# PLL2.net
KiCad netlist of a schematic drawn in Altium Designer
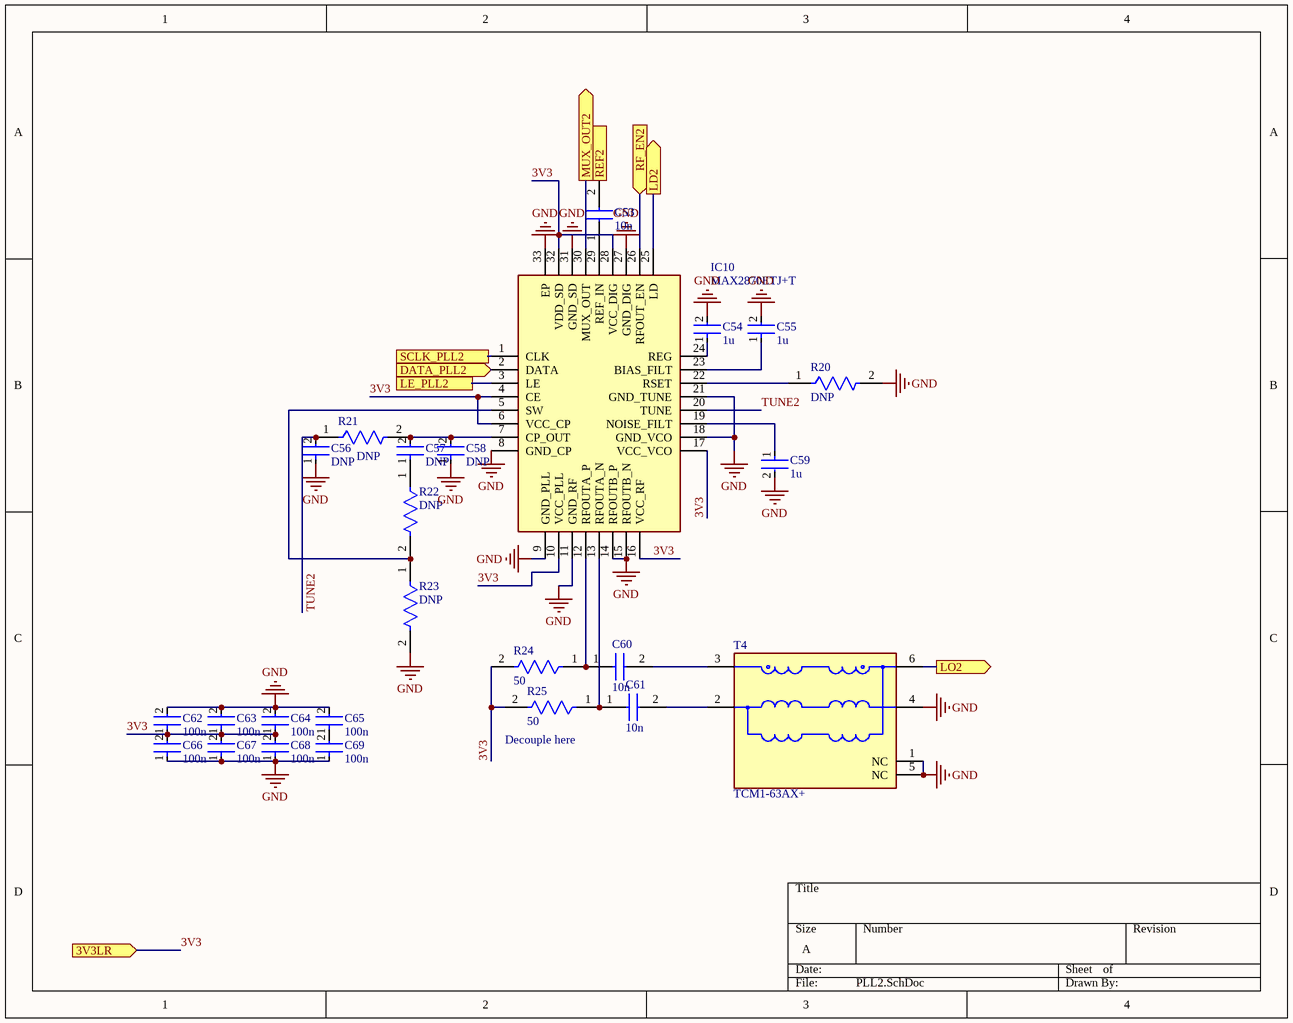
[diagram p0: PLL2.SchDoc]

(export (version "E")
  (design (tool "Eeschema 10.0.6"))
  (components
    (comp (ref "C53")
      (value "10n")
      (footprint "SamacSys:CAPC1005X61N")
      (description "Capacitor")
      (fields
        (field (name "MANUFACTURER_PART_NUMBER") "520L103KT16T")
        (field (name "MOUSER PART NUMBER") "581-520L103KT16T")
      )
      (libsource (lib "*") (part "520L103KT16T"))
    )
    (comp (ref "C54")
      (value "1u")
      (footprint "FP-GRM155-0_1-MFG")
      (description "Chip Multilayer Ceramic Capacitors for General Purpose, 0402, 1.0uF, X5R, 15%, 10%, 50V")
      (libsource (lib "Altium Content Vault") (part "11868f565c42a9108669ba33697ecf6"))
    )
    (comp (ref "C55")
      (value "1u")
      (footprint "FP-GRM155-0_1-MFG")
      (description "Chip Multilayer Ceramic Capacitors for General Purpose, 0402, 1.0uF, X5R, 15%, 10%, 50V")
      (libsource (lib "Altium Content Vault") (part "11868f565c42a9108669ba33697ecf6"))
    )
    (comp (ref "C56")
      (value "DNP")
      (footprint "FP-GRM155-0_05-IPC_C")
      (description "Chip Multilayer Ceramic Capacitors for General Purpose, 0402, 0.10uF, X5R, 15%, 10%, 100V")
      (fields (field (name "TOLERANCE") "10%"))
      (libsource (lib "Altium Content Vault") (part "02cd4be3c70576c341d710602a673aa"))
    )
    (comp (ref "C57")
      (value "DNP")
      (footprint "FP-GRM155-0_05-IPC_C")
      (description "Chip Multilayer Ceramic Capacitors for General Purpose, 0402, 0.10uF, X5R, 15%, 10%, 100V")
      (fields (field (name "TOLERANCE") "10%"))
      (libsource (lib "Altium Content Vault") (part "02cd4be3c70576c341d710602a673aa"))
    )
    (comp (ref "C58")
      (value "DNP")
      (footprint "FP-GRM155-0_05-IPC_C")
      (description "Chip Multilayer Ceramic Capacitors for General Purpose, 0402, 0.10uF, X5R, 15%, 10%, 100V")
      (fields (field (name "TOLERANCE") "10%"))
      (libsource (lib "Altium Content Vault") (part "02cd4be3c70576c341d710602a673aa"))
    )
    (comp (ref "C59")
      (value "1u")
      (footprint "FP-GRM155-0_1-MFG")
      (description "Chip Multilayer Ceramic Capacitors for General Purpose, 0402, 1.0uF, X5R, 15%, 10%, 50V")
      (libsource (lib "Altium Content Vault") (part "11868f565c42a9108669ba33697ecf6"))
    )
    (comp (ref "C60")
      (value "10n")
      (footprint "SamacSys:CAPC1005X61N")
      (description "Capacitor")
      (fields
        (field (name "MANUFACTURER_PART_NUMBER") "520L103KT16T")
        (field (name "MOUSER PART NUMBER") "581-520L103KT16T")
      )
      (libsource (lib "*") (part "520L103KT16T"))
    )
    (comp (ref "C61")
      (value "10n")
      (footprint "SamacSys:CAPC1005X61N")
      (description "Capacitor")
      (fields
        (field (name "MANUFACTURER_PART_NUMBER") "520L103KT16T")
        (field (name "MOUSER PART NUMBER") "581-520L103KT16T")
      )
      (libsource (lib "*") (part "520L103KT16T"))
    )
    (comp (ref "C62")
      (value "100n")
      (footprint "FP-GRM155-0_05-IPC_C")
      (description "Chip Multilayer Ceramic Capacitors for General Purpose, 0402, 0.10uF, X5R, 15%, 10%, 100V")
      (fields (field (name "TOLERANCE") "10%"))
      (libsource (lib "Altium Content Vault") (part "02cd4be3c70576c341d710602a673aa"))
    )
    (comp (ref "C63")
      (value "100n")
      (footprint "FP-GRM155-0_05-IPC_C")
      (description "Chip Multilayer Ceramic Capacitors for General Purpose, 0402, 0.10uF, X5R, 15%, 10%, 100V")
      (fields (field (name "TOLERANCE") "10%"))
      (libsource (lib "Altium Content Vault") (part "02cd4be3c70576c341d710602a673aa"))
    )
    (comp (ref "C64")
      (value "100n")
      (footprint "FP-GRM155-0_05-IPC_C")
      (description "Chip Multilayer Ceramic Capacitors for General Purpose, 0402, 0.10uF, X5R, 15%, 10%, 100V")
      (fields (field (name "TOLERANCE") "10%"))
      (libsource (lib "Altium Content Vault") (part "02cd4be3c70576c341d710602a673aa"))
    )
    (comp (ref "C65")
      (value "100n")
      (footprint "FP-GRM155-0_05-IPC_C")
      (description "Chip Multilayer Ceramic Capacitors for General Purpose, 0402, 0.10uF, X5R, 15%, 10%, 100V")
      (fields (field (name "TOLERANCE") "10%"))
      (libsource (lib "Altium Content Vault") (part "02cd4be3c70576c341d710602a673aa"))
    )
    (comp (ref "C66")
      (value "100n")
      (footprint "FP-GRM155-0_05-IPC_C")
      (description "Chip Multilayer Ceramic Capacitors for General Purpose, 0402, 0.10uF, X5R, 15%, 10%, 100V")
      (fields (field (name "TOLERANCE") "10%"))
      (libsource (lib "Altium Content Vault") (part "02cd4be3c70576c341d710602a673aa"))
    )
    (comp (ref "C67")
      (value "100n")
      (footprint "FP-GRM155-0_05-IPC_C")
      (description "Chip Multilayer Ceramic Capacitors for General Purpose, 0402, 0.10uF, X5R, 15%, 10%, 100V")
      (fields (field (name "TOLERANCE") "10%"))
      (libsource (lib "Altium Content Vault") (part "02cd4be3c70576c341d710602a673aa"))
    )
    (comp (ref "C68")
      (value "100n")
      (footprint "FP-GRM155-0_05-IPC_C")
      (description "Chip Multilayer Ceramic Capacitors for General Purpose, 0402, 0.10uF, X5R, 15%, 10%, 100V")
      (fields (field (name "TOLERANCE") "10%"))
      (libsource (lib "Altium Content Vault") (part "02cd4be3c70576c341d710602a673aa"))
    )
    (comp (ref "C69")
      (value "100n")
      (footprint "FP-GRM155-0_05-IPC_C")
      (description "Chip Multilayer Ceramic Capacitors for General Purpose, 0402, 0.10uF, X5R, 15%, 10%, 100V")
      (fields (field (name "TOLERANCE") "10%"))
      (libsource (lib "Altium Content Vault") (part "02cd4be3c70576c341d710602a673aa"))
    )
    (comp (ref "IC10")
      (value "MAX2870ETJ+T")
      (footprint "SamacSys:QFN50P500X500X80-33N")
      (description "Integrated Circuit")
      (fields (field (name "MOUSER PART NUMBER") "700-MAX2870ETJ+T"))
      (libsource (lib "*") (part "MAX2870ETJ+T"))
    )
    (comp (ref "R20")
      (value "DNP")
      (footprint "FP-AC0402-IPC_B")
      (description "RES 13.3kΩ ±1% 0.063W 0402")
      (fields (field (name "TOLERANCE") "1%"))
      (libsource (lib "Altium Content Vault") (part "1029c3af85768c4190bb7ad29bc67b5"))
    )
    (comp (ref "R21")
      (value "DNP")
      (footprint "FP-AC0402-IPC_B")
      (description "RES 13.3kΩ ±1% 0.063W 0402")
      (fields (field (name "TOLERANCE") "1%"))
      (libsource (lib "Altium Content Vault") (part "1029c3af85768c4190bb7ad29bc67b5"))
    )
    (comp (ref "R22")
      (value "DNP")
      (footprint "FP-AC0402-IPC_B")
      (description "RES 13.3kΩ ±1% 0.063W 0402")
      (fields (field (name "TOLERANCE") "1%"))
      (libsource (lib "Altium Content Vault") (part "1029c3af85768c4190bb7ad29bc67b5"))
    )
    (comp (ref "R23")
      (value "DNP")
      (footprint "FP-AC0402-IPC_B")
      (description "RES 13.3kΩ ±1% 0.063W 0402")
      (fields (field (name "TOLERANCE") "1%"))
      (libsource (lib "Altium Content Vault") (part "1029c3af85768c4190bb7ad29bc67b5"))
    )
    (comp (ref "R24")
      (value "50")
      (footprint "FP-RC0402-0_4-MFG")
      (fields (field (name "TOLERANCE") "5%"))
      (libsource (lib "Altium Content Vault") (part "1029c3af85768c4190bb7ad29bc67b5"))
    )
    (comp (ref "R25")
      (value "50")
      (footprint "FP-RC0402-0_4-MFG")
      (fields (field (name "TOLERANCE") "5%"))
      (libsource (lib "Altium Content Vault") (part "1029c3af85768c4190bb7ad29bc67b5"))
    )
    (comp (ref "T4")
      (value "TCM1-63AX+")
      (footprint "FP-TCM1-63AX+-MFG")
      (description "1:1 CORE & WIRE Transformer, 10 - 6000 MHz, 50Ω")
      (fields
        (field (name "MANUFACTURER") "Mini-Circuits")
        (field (name "OCTOPART") "https://octopart.com/tcm1-63ax%2B-mini-circuits-107315723")
      )
      (libsource (lib "Altium Content Vault") (part "572340aedd709dbafee1a1d3331a406"))
    )
  )
  (nets
    (net (code "1") (name "/3V3") (class "Default")
      (node (ref "C62") (pin "1") (pinfunction "1_1") (pintype "passive"))
      (node (ref "C63") (pin "1") (pinfunction "1_1") (pintype "passive"))
      (node (ref "C64") (pin "1") (pinfunction "1_1") (pintype "passive"))
      (node (ref "C66") (pin "2") (pinfunction "2_2") (pintype "passive"))
      (node (ref "C67") (pin "2") (pinfunction "2_2") (pintype "passive"))
      (node (ref "C68") (pin "2") (pinfunction "2_2") (pintype "passive"))
      (node (ref "IC10") (pin "10") (pinfunction "VCC_PLL_10") (pintype "passive"))
      (node (ref "IC10") (pin "16") (pinfunction "VCC_RF_16") (pintype "passive"))
      (node (ref "IC10") (pin "17") (pinfunction "VCC_VCO_17") (pintype "passive"))
      (node (ref "IC10") (pin "28") (pinfunction "VCC_DIG_28") (pintype "passive"))
      (node (ref "IC10") (pin "32") (pinfunction "VDD_SD_32") (pintype "passive"))
      (node (ref "IC10") (pin "4") (pinfunction "CE_4") (pintype "passive"))
      (node (ref "IC10") (pin "6") (pinfunction "VCC_CP_6") (pintype "passive"))
      (node (ref "R24") (pin "2") (pinfunction "2_2") (pintype "passive"))
      (node (ref "R25") (pin "2") (pinfunction "2_2") (pintype "passive"))
    )
    (net (code "2") (name "/DATA_PLL2") (class "Default")
      (node (ref "IC10") (pin "2") (pinfunction "DATA_2") (pintype "passive"))
    )
    (net (code "3") (name "/LD2") (class "Default")
      (node (ref "IC10") (pin "25") (pinfunction "LD_25") (pintype "passive"))
    )
    (net (code "4") (name "/LE_PLL2") (class "Default")
      (node (ref "IC10") (pin "3") (pinfunction "LE_3") (pintype "passive"))
    )
    (net (code "5") (name "/LO2") (class "Default")
      (node (ref "T4") (pin "6") (pinfunction "SECONDARY_DOT_6") (pintype "passive"))
    )
    (net (code "6") (name "/MUX_OUT2") (class "Default")
      (node (ref "IC10") (pin "30") (pinfunction "MUX_OUT_30") (pintype "passive"))
    )
    (net (code "7") (name "/REF2") (class "Default")
      (node (ref "C53") (pin "2") (pinfunction "2_2") (pintype "passive"))
    )
    (net (code "8") (name "/RF_EN2") (class "Default")
      (node (ref "IC10") (pin "26") (pinfunction "RFOUT_EN_26") (pintype "passive"))
    )
    (net (code "9") (name "/SCLK_PLL2") (class "Default")
      (node (ref "IC10") (pin "1") (pinfunction "CLK_1") (pintype "passive"))
    )
    (net (code "10") (name "/TUNE2") (class "Default")
      (node (ref "C56") (pin "2") (pinfunction "2_2") (pintype "passive"))
      (node (ref "IC10") (pin "20") (pinfunction "TUNE_20") (pintype "passive"))
      (node (ref "R21") (pin "1") (pinfunction "1_1") (pintype "passive"))
    )
    (net (code "11") (name "GND") (class "Default")
      (node (ref "C54") (pin "2") (pinfunction "2_2") (pintype "passive"))
      (node (ref "C55") (pin "2") (pinfunction "2_2") (pintype "passive"))
      (node (ref "C56") (pin "1") (pinfunction "1_1") (pintype "passive"))
      (node (ref "C58") (pin "1") (pinfunction "1_1") (pintype "passive"))
      (node (ref "C59") (pin "2") (pinfunction "2_2") (pintype "passive"))
      (node (ref "C62") (pin "2") (pinfunction "2_2") (pintype "passive"))
      (node (ref "C63") (pin "2") (pinfunction "2_2") (pintype "passive"))
      (node (ref "C64") (pin "2") (pinfunction "2_2") (pintype "passive"))
      (node (ref "C65") (pin "2") (pinfunction "2_2") (pintype "passive"))
      (node (ref "C66") (pin "1") (pinfunction "1_1") (pintype "passive"))
      (node (ref "C67") (pin "1") (pinfunction "1_1") (pintype "passive"))
      (node (ref "C68") (pin "1") (pinfunction "1_1") (pintype "passive"))
      (node (ref "C69") (pin "1") (pinfunction "1_1") (pintype "passive"))
      (node (ref "IC10") (pin "11") (pinfunction "GND_RF_11") (pintype "passive"))
      (node (ref "IC10") (pin "14") (pinfunction "RFOUTB_P_14") (pintype "passive"))
      (node (ref "IC10") (pin "15") (pinfunction "RFOUTB_N_15") (pintype "passive"))
      (node (ref "IC10") (pin "18") (pinfunction "GND_VCO_18") (pintype "passive"))
      (node (ref "IC10") (pin "21") (pinfunction "GND_TUNE_21") (pintype "passive"))
      (node (ref "IC10") (pin "27") (pinfunction "GND_DIG_27") (pintype "passive"))
      (node (ref "IC10") (pin "31") (pinfunction "GND_SD_31") (pintype "passive"))
      (node (ref "IC10") (pin "33") (pinfunction "EP_33") (pintype "passive"))
      (node (ref "IC10") (pin "8") (pinfunction "GND_CP_8") (pintype "passive"))
      (node (ref "IC10") (pin "9") (pinfunction "GND_PLL_9") (pintype "passive"))
      (node (ref "R20") (pin "2") (pinfunction "2_2") (pintype "passive"))
      (node (ref "R23") (pin "2") (pinfunction "2_2") (pintype "passive"))
      (node (ref "T4") (pin "1") (pinfunction "NC_1") (pintype "passive"))
      (node (ref "T4") (pin "4") (pinfunction "SECONDARY_4") (pintype "passive"))
      (node (ref "T4") (pin "5") (pinfunction "NC_5") (pintype "passive"))
    )
    (net (code "12") (name "Net-(C57-Pad1)") (class "Default")
      (node (ref "C57") (pin "1") (pinfunction "1_1") (pintype "passive"))
      (node (ref "R22") (pin "1") (pinfunction "1_1") (pintype "passive"))
    )
    (net (code "13") (name "Net-(C65-Pad1)") (class "Default")
      (node (ref "C65") (pin "1") (pinfunction "1_1") (pintype "passive"))
      (node (ref "C69") (pin "2") (pinfunction "2_2") (pintype "passive"))
    )
    (net (code "14") (name "Net-(IC10-BIAS_FILT)") (class "Default")
      (node (ref "C55") (pin "1") (pinfunction "1_1") (pintype "passive"))
      (node (ref "IC10") (pin "23") (pinfunction "BIAS_FILT_23") (pintype "passive"))
    )
    (net (code "15") (name "Net-(IC10-CP_OUT)") (class "Default")
      (node (ref "C57") (pin "2") (pinfunction "2_2") (pintype "passive"))
      (node (ref "C58") (pin "2") (pinfunction "2_2") (pintype "passive"))
      (node (ref "IC10") (pin "7") (pinfunction "CP_OUT_7") (pintype "passive"))
      (node (ref "R21") (pin "2") (pinfunction "2_2") (pintype "passive"))
    )
    (net (code "16") (name "Net-(IC10-NOISE_FILT)") (class "Default")
      (node (ref "C59") (pin "1") (pinfunction "1_1") (pintype "passive"))
      (node (ref "IC10") (pin "19") (pinfunction "NOISE_FILT_19") (pintype "passive"))
    )
    (net (code "17") (name "Net-(IC10-REF_IN)") (class "Default")
      (node (ref "C53") (pin "1") (pinfunction "1_1") (pintype "passive"))
      (node (ref "IC10") (pin "29") (pinfunction "REF_IN_29") (pintype "passive"))
    )
    (net (code "18") (name "Net-(IC10-REG)") (class "Default")
      (node (ref "C54") (pin "1") (pinfunction "1_1") (pintype "passive"))
      (node (ref "IC10") (pin "24") (pinfunction "REG_24") (pintype "passive"))
    )
    (net (code "19") (name "Net-(IC10-RFOUTA_N)") (class "Default")
      (node (ref "C61") (pin "1") (pinfunction "1_1") (pintype "passive"))
      (node (ref "IC10") (pin "13") (pinfunction "RFOUTA_N_13") (pintype "passive"))
      (node (ref "R25") (pin "1") (pinfunction "1_1") (pintype "passive"))
    )
    (net (code "20") (name "Net-(IC10-RFOUTA_P)") (class "Default")
      (node (ref "C60") (pin "1") (pinfunction "1_1") (pintype "passive"))
      (node (ref "IC10") (pin "12") (pinfunction "RFOUTA_P_12") (pintype "passive"))
      (node (ref "R24") (pin "1") (pinfunction "1_1") (pintype "passive"))
    )
    (net (code "21") (name "Net-(IC10-RSET)") (class "Default")
      (node (ref "IC10") (pin "22") (pinfunction "RSET_22") (pintype "passive"))
      (node (ref "R20") (pin "1") (pinfunction "1_1") (pintype "passive"))
    )
    (net (code "22") (name "Net-(IC10-SW)") (class "Default")
      (node (ref "IC10") (pin "5") (pinfunction "SW_5") (pintype "passive"))
      (node (ref "R22") (pin "2") (pinfunction "2_2") (pintype "passive"))
      (node (ref "R23") (pin "1") (pinfunction "1_1") (pintype "passive"))
    )
    (net (code "23") (name "Net-(T4-GND)") (class "Default")
      (node (ref "C61") (pin "2") (pinfunction "2_2") (pintype "passive"))
      (node (ref "T4") (pin "2") (pinfunction "GND_2") (pintype "passive"))
    )
    (net (code "24") (name "Net-(T4-PRIMARY_DOT)") (class "Default")
      (node (ref "C60") (pin "2") (pinfunction "2_2") (pintype "passive"))
      (node (ref "T4") (pin "3") (pinfunction "PRIMARY_DOT_3") (pintype "passive"))
    )
  )
)
